# Connectors.net
KiCad netlist of a schematic drawn in Altium Designer
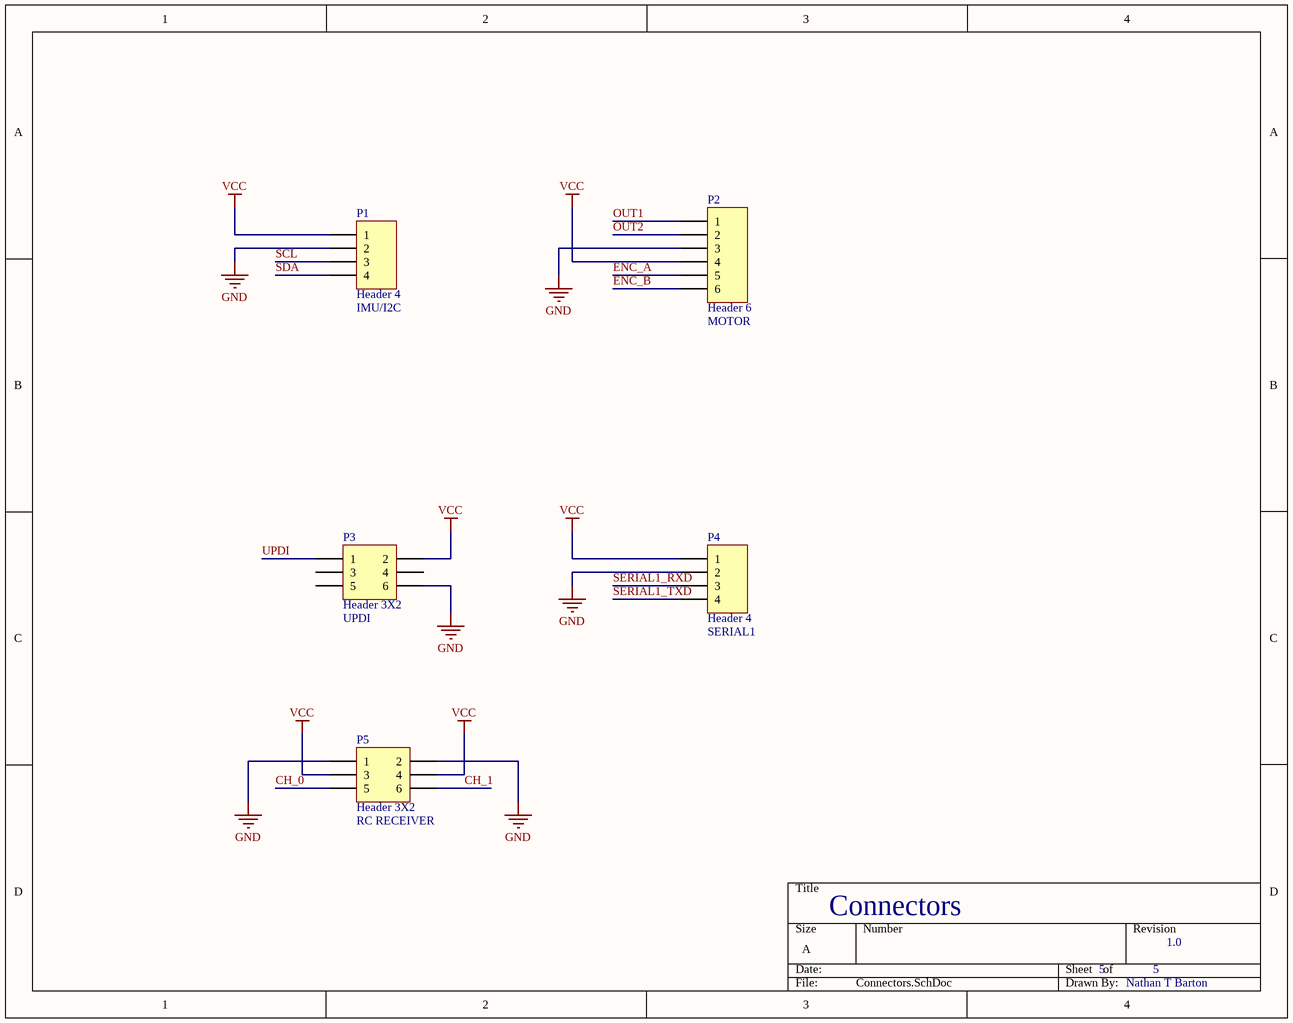
[diagram p0: Connectors.SchDoc]

(export (version "E")
  (design (tool "Eeschema 10.0.6"))
  (components
    (comp (ref "P1")
      (value "Header 4")
      (footprint "HDR1X4")
      (description "Header, 4-Pin")
      (fields (field (name "PUBLISHER") "Altium Limited"))
      (libsource (lib "Miscellaneous Connectors") (part "Header 4"))
    )
    (comp (ref "P2")
      (value "Header 6")
      (footprint "HDR1X6")
      (description "Header, 6-Pin")
      (fields (field (name "PUBLISHER") "Altium Limited"))
      (libsource (lib "Miscellaneous Connectors") (part "Header 6"))
    )
    (comp (ref "P3")
      (value "Header 3X2")
      (footprint "HDR2X3")
      (description "Header, 3-Pin, Dual row")
      (fields (field (name "PUBLISHER") "Altium Limited"))
      (libsource (lib "Miscellaneous Connectors") (part "Header 3X2"))
    )
    (comp (ref "P4")
      (value "Header 4")
      (footprint "HDR1X4")
      (description "Header, 4-Pin")
      (fields (field (name "PUBLISHER") "Altium Limited"))
      (libsource (lib "Miscellaneous Connectors") (part "Header 4"))
    )
    (comp (ref "P5")
      (value "Header 3X2")
      (footprint "HDR2X3")
      (description "Header, 3-Pin, Dual row")
      (fields (field (name "PUBLISHER") "Altium Limited"))
      (libsource (lib "Miscellaneous Connectors") (part "Header 3X2"))
    )
  )
  (nets
    (net (code "1") (name "/CH_0") (class "Default")
      (node (ref "P5") (pin "5") (pinfunction "5_5") (pintype "passive"))
    )
    (net (code "2") (name "/CH_1") (class "Default")
      (node (ref "P5") (pin "6") (pinfunction "6_6") (pintype "passive"))
    )
    (net (code "3") (name "/ENC_A") (class "Default")
      (node (ref "P2") (pin "5") (pinfunction "5_5") (pintype "passive"))
    )
    (net (code "4") (name "/ENC_B") (class "Default")
      (node (ref "P2") (pin "6") (pinfunction "6_6") (pintype "passive"))
    )
    (net (code "5") (name "/OUT1") (class "Default")
      (node (ref "P2") (pin "1") (pinfunction "1_1") (pintype "passive"))
    )
    (net (code "6") (name "/OUT2") (class "Default")
      (node (ref "P2") (pin "2") (pinfunction "2_2") (pintype "passive"))
    )
    (net (code "7") (name "/SCL") (class "Default")
      (node (ref "P1") (pin "3") (pinfunction "3_3") (pintype "passive"))
    )
    (net (code "8") (name "/SDA") (class "Default")
      (node (ref "P1") (pin "4") (pinfunction "4_4") (pintype "passive"))
    )
    (net (code "9") (name "/SERIAL1_RXD") (class "Default")
      (node (ref "P4") (pin "3") (pinfunction "3_3") (pintype "passive"))
    )
    (net (code "10") (name "/SERIAL1_TXD") (class "Default")
      (node (ref "P4") (pin "4") (pinfunction "4_4") (pintype "passive"))
    )
    (net (code "11") (name "/UPDI") (class "Default")
      (node (ref "P3") (pin "1") (pinfunction "1_1") (pintype "passive"))
    )
    (net (code "12") (name "GND") (class "Default")
      (node (ref "P1") (pin "2") (pinfunction "2_2") (pintype "passive"))
      (node (ref "P2") (pin "3") (pinfunction "3_3") (pintype "passive"))
      (node (ref "P3") (pin "6") (pinfunction "6_6") (pintype "passive"))
      (node (ref "P4") (pin "2") (pinfunction "2_2") (pintype "passive"))
      (node (ref "P5") (pin "1") (pinfunction "1_1") (pintype "passive"))
      (node (ref "P5") (pin "2") (pinfunction "2_2") (pintype "passive"))
    )
    (net (code "13") (name "VCC") (class "Default")
      (node (ref "P1") (pin "1") (pinfunction "1_1") (pintype "passive"))
      (node (ref "P2") (pin "4") (pinfunction "4_4") (pintype "passive"))
      (node (ref "P3") (pin "2") (pinfunction "2_2") (pintype "passive"))
      (node (ref "P4") (pin "1") (pinfunction "1_1") (pintype "passive"))
      (node (ref "P5") (pin "3") (pinfunction "3_3") (pintype "passive"))
      (node (ref "P5") (pin "4") (pinfunction "4_4") (pintype "passive"))
    )
    (net (code "14") (name "unconnected-(P3-Pad3)") (class "Default")
      (node (ref "P3") (pin "3") (pinfunction "3_3") (pintype "passive"))
    )
    (net (code "15") (name "unconnected-(P3-Pad4)") (class "Default")
      (node (ref "P3") (pin "4") (pinfunction "4_4") (pintype "passive"))
    )
    (net (code "16") (name "unconnected-(P3-Pad5)") (class "Default")
      (node (ref "P3") (pin "5") (pinfunction "5_5") (pintype "passive"))
    )
  )
)
